# prescaled_trigger.net
KiCad netlist of a schematic drawn in EAGLE
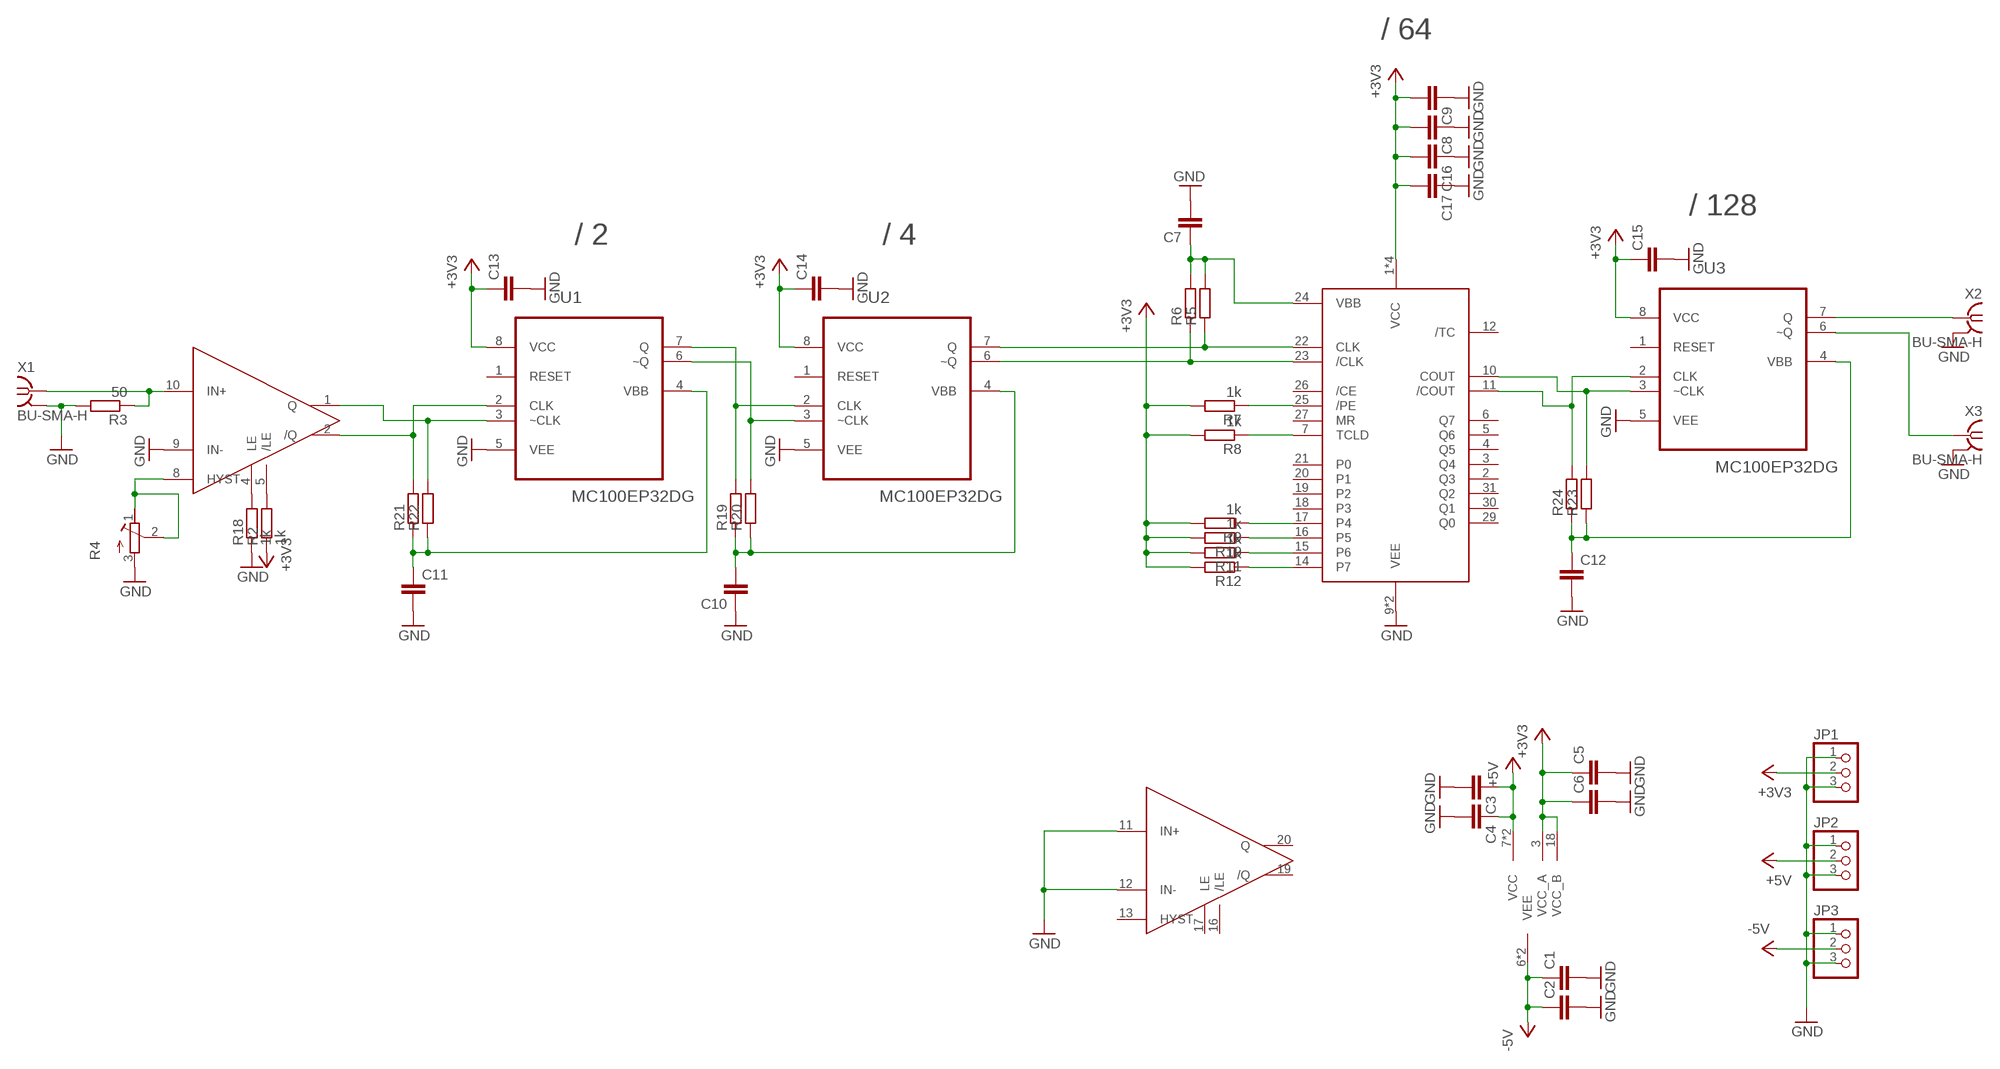
[diagram p0: schematic, sheet 1]

(export (version "E")
  (design (tool "Eeschema 10.0.6"))
  (components
    (comp (ref "C1")
      (value "C-EUC0805")
      (footprint "eagle-import:C0805")
      (libsource (lib "eagle-import") (part "C-EUC0805"))
    )
    (comp (ref "C2")
      (value "C-EUC0805")
      (footprint "eagle-import:C0805")
      (libsource (lib "eagle-import") (part "C-EUC0805"))
    )
    (comp (ref "C3")
      (value "C-EUC0805")
      (footprint "eagle-import:C0805")
      (libsource (lib "eagle-import") (part "C-EUC0805"))
    )
    (comp (ref "C4")
      (value "C-EUC0805")
      (footprint "eagle-import:C0805")
      (libsource (lib "eagle-import") (part "C-EUC0805"))
    )
    (comp (ref "C5")
      (value "C-EUC0805")
      (footprint "eagle-import:C0805")
      (libsource (lib "eagle-import") (part "C-EUC0805"))
    )
    (comp (ref "C6")
      (value "C-EUC0805")
      (footprint "eagle-import:C0805")
      (libsource (lib "eagle-import") (part "C-EUC0805"))
    )
    (comp (ref "C7")
      (value "C-EUC0805")
      (footprint "eagle-import:C0805")
      (libsource (lib "eagle-import") (part "C-EUC0805"))
    )
    (comp (ref "C8")
      (value "C-EUC0805")
      (footprint "eagle-import:C0805")
      (libsource (lib "eagle-import") (part "C-EUC0805"))
    )
    (comp (ref "C9")
      (value "C-EUC0805")
      (footprint "eagle-import:C0805")
      (libsource (lib "eagle-import") (part "C-EUC0805"))
    )
    (comp (ref "C10")
      (value "C-EUC0805")
      (footprint "eagle-import:C0805")
      (libsource (lib "eagle-import") (part "C-EUC0805"))
    )
    (comp (ref "C11")
      (value "C-EUC0805")
      (footprint "eagle-import:C0805")
      (libsource (lib "eagle-import") (part "C-EUC0805"))
    )
    (comp (ref "C12")
      (value "C-EUC0805")
      (footprint "eagle-import:C0805")
      (libsource (lib "eagle-import") (part "C-EUC0805"))
    )
    (comp (ref "C13")
      (value "C-EUC0805")
      (footprint "eagle-import:C0805")
      (libsource (lib "eagle-import") (part "C-EUC0805"))
    )
    (comp (ref "C14")
      (value "C-EUC0805")
      (footprint "eagle-import:C0805")
      (libsource (lib "eagle-import") (part "C-EUC0805"))
    )
    (comp (ref "C15")
      (value "C-EUC0805")
      (footprint "eagle-import:C0805")
      (libsource (lib "eagle-import") (part "C-EUC0805"))
    )
    (comp (ref "C16")
      (value "C-EUC0805")
      (footprint "eagle-import:C0805")
      (libsource (lib "eagle-import") (part "C-EUC0805"))
    )
    (comp (ref "C17")
      (value "C-EUC0805")
      (footprint "eagle-import:C0805")
      (libsource (lib "eagle-import") (part "C-EUC0805"))
    )
    (comp (ref "JP1")
      (value "PINHD-1X3")
      (footprint "eagle-import:1X03")
      (libsource (lib "eagle-import") (part "PINHD-1X3"))
    )
    (comp (ref "JP2")
      (value "PINHD-1X3")
      (footprint "eagle-import:1X03")
      (libsource (lib "eagle-import") (part "PINHD-1X3"))
    )
    (comp (ref "JP3")
      (value "PINHD-1X3")
      (footprint "eagle-import:1X03")
      (libsource (lib "eagle-import") (part "PINHD-1X3"))
    )
    (comp (ref "R2")
      (value "1k")
      (footprint "eagle-import:M0805")
      (libsource (lib "eagle-import") (part "R-EU_M0805"))
    )
    (comp (ref "R3")
      (value "50")
      (footprint "eagle-import:M0805")
      (libsource (lib "eagle-import") (part "R-EU_M0805"))
    )
    (comp (ref "R4")
      (value "R-TRIMMT18")
      (footprint "eagle-import:RTRIMT18")
      (libsource (lib "eagle-import") (part "R-TRIMMT18"))
    )
    (comp (ref "R5")
      (value "R-EU_M1206")
      (footprint "eagle-import:M1206")
      (libsource (lib "eagle-import") (part "R-EU_M1206"))
    )
    (comp (ref "R6")
      (value "R-EU_M1206")
      (footprint "eagle-import:M1206")
      (libsource (lib "eagle-import") (part "R-EU_M1206"))
    )
    (comp (ref "R7")
      (value "1k")
      (footprint "eagle-import:M0805")
      (libsource (lib "eagle-import") (part "R-EU_M0805"))
    )
    (comp (ref "R8")
      (value "1k")
      (footprint "eagle-import:M0805")
      (libsource (lib "eagle-import") (part "R-EU_M0805"))
    )
    (comp (ref "R9")
      (value "1k")
      (footprint "eagle-import:M0805")
      (libsource (lib "eagle-import") (part "R-EU_M0805"))
    )
    (comp (ref "R10")
      (value "1k")
      (footprint "eagle-import:M0805")
      (libsource (lib "eagle-import") (part "R-EU_M0805"))
    )
    (comp (ref "R11")
      (value "1k")
      (footprint "eagle-import:M0805")
      (libsource (lib "eagle-import") (part "R-EU_M0805"))
    )
    (comp (ref "R12")
      (value "1k")
      (footprint "eagle-import:M0805")
      (libsource (lib "eagle-import") (part "R-EU_M0805"))
    )
    (comp (ref "R18")
      (value "1k")
      (footprint "eagle-import:M0805")
      (libsource (lib "eagle-import") (part "R-EU_M0805"))
    )
    (comp (ref "R19")
      (value "R-EU_M1206")
      (footprint "eagle-import:M1206")
      (libsource (lib "eagle-import") (part "R-EU_M1206"))
    )
    (comp (ref "R20")
      (value "R-EU_M1206")
      (footprint "eagle-import:M1206")
      (libsource (lib "eagle-import") (part "R-EU_M1206"))
    )
    (comp (ref "R21")
      (value "R-EU_M1206")
      (footprint "eagle-import:M1206")
      (libsource (lib "eagle-import") (part "R-EU_M1206"))
    )
    (comp (ref "R22")
      (value "R-EU_M1206")
      (footprint "eagle-import:M1206")
      (libsource (lib "eagle-import") (part "R-EU_M1206"))
    )
    (comp (ref "R23")
      (value "R-EU_M1206")
      (footprint "eagle-import:M1206")
      (libsource (lib "eagle-import") (part "R-EU_M1206"))
    )
    (comp (ref "R24")
      (value "R-EU_M1206")
      (footprint "eagle-import:M1206")
      (libsource (lib "eagle-import") (part "R-EU_M1206"))
    )
    (comp (ref "U$1")
      (value "MAX9601")
      (footprint "eagle-import:SSOP20DB")
      (libsource (lib "eagle-import") (part "MAX9601"))
    )
    (comp (ref "U$2")
      (value "MC100EP016")
      (footprint "eagle-import:QFP80P900X900X160-32N")
      (libsource (lib "eagle-import") (part "MC100EP016"))
    )
    (comp (ref "U1")
      (value "MC100EP32DG")
      (footprint "eagle-import:SOIC127P600X175-8N")
      (libsource (lib "eagle-import") (part "MC100EP32DG"))
    )
    (comp (ref "U2")
      (value "MC100EP32DG")
      (footprint "eagle-import:SOIC127P600X175-8N")
      (libsource (lib "eagle-import") (part "MC100EP32DG"))
    )
    (comp (ref "U3")
      (value "MC100EP32DG")
      (footprint "eagle-import:SOIC127P600X175-8N")
      (libsource (lib "eagle-import") (part "MC100EP32DG"))
    )
    (comp (ref "X1")
      (value "BU-SMA-H")
      (footprint "eagle-import:BU-SMA-H")
      (libsource (lib "eagle-import") (part "BU-SMA-H"))
    )
    (comp (ref "X2")
      (value "BU-SMA-H")
      (footprint "eagle-import:BU-SMA-H")
      (libsource (lib "eagle-import") (part "BU-SMA-H"))
    )
    (comp (ref "X3")
      (value "BU-SMA-H")
      (footprint "eagle-import:BU-SMA-H")
      (libsource (lib "eagle-import") (part "BU-SMA-H"))
    )
  )
  (nets
    (net (code "1") (name "+3V3") (class "Default")
      (node (ref "C13") (pin "1") (pinfunction "1_1") (pintype "passive"))
      (node (ref "C14") (pin "1") (pinfunction "1_1") (pintype "passive"))
      (node (ref "C15") (pin "1") (pinfunction "1_1") (pintype "passive"))
      (node (ref "C16") (pin "2") (pinfunction "2_2") (pintype "passive"))
      (node (ref "C17") (pin "2") (pinfunction "2_2") (pintype "passive"))
      (node (ref "C5") (pin "1") (pinfunction "1_1") (pintype "passive"))
      (node (ref "C6") (pin "1") (pinfunction "1_1") (pintype "passive"))
      (node (ref "C8") (pin "2") (pinfunction "2_2") (pintype "passive"))
      (node (ref "C9") (pin "2") (pinfunction "2_2") (pintype "passive"))
      (node (ref "JP1") (pin "2") (pinfunction "2_2") (pintype "passive"))
      (node (ref "R10") (pin "2") (pinfunction "2_2") (pintype "passive"))
      (node (ref "R11") (pin "2") (pinfunction "2_2") (pintype "passive"))
      (node (ref "R12") (pin "2") (pinfunction "2_2") (pintype "passive"))
      (node (ref "R2") (pin "1") (pinfunction "1_1") (pintype "passive"))
      (node (ref "R7") (pin "2") (pinfunction "2_2") (pintype "passive"))
      (node (ref "R8") (pin "2") (pinfunction "2_2") (pintype "passive"))
      (node (ref "R9") (pin "2") (pinfunction "2_2") (pintype "passive"))
      (node (ref "U$1") (pin "18") (pinfunction "VCC_B_18") (pintype "bidirectional"))
      (node (ref "U$1") (pin "3") (pinfunction "VCC_A_3") (pintype "bidirectional"))
      (node (ref "U$2") (pin "1") (pinfunction "VCC_1") (pintype "bidirectional"))
      (node (ref "U$2") (pin "13") (pinfunction "VCC_13") (pintype "bidirectional"))
      (node (ref "U$2") (pin "32") (pinfunction "VCC_32") (pintype "bidirectional"))
      (node (ref "U$2") (pin "8") (pinfunction "VCC_8") (pintype "bidirectional"))
      (node (ref "U1") (pin "8") (pinfunction "VCC_8") (pintype "power_in"))
      (node (ref "U2") (pin "8") (pinfunction "VCC_8") (pintype "power_in"))
      (node (ref "U3") (pin "8") (pinfunction "VCC_8") (pintype "power_in"))
    )
    (net (code "2") (name "+5V") (class "Default")
      (node (ref "C3") (pin "1") (pinfunction "1_1") (pintype "passive"))
      (node (ref "C4") (pin "1") (pinfunction "1_1") (pintype "passive"))
      (node (ref "JP2") (pin "2") (pinfunction "2_2") (pintype "passive"))
      (node (ref "U$1") (pin "14") (pinfunction "VCC_14") (pintype "bidirectional"))
      (node (ref "U$1") (pin "7") (pinfunction "VCC_7") (pintype "bidirectional"))
    )
    (net (code "3") (name "-5V") (class "Default")
      (node (ref "C1") (pin "1") (pinfunction "1_1") (pintype "passive"))
      (node (ref "C2") (pin "1") (pinfunction "1_1") (pintype "passive"))
      (node (ref "JP3") (pin "2") (pinfunction "2_2") (pintype "passive"))
      (node (ref "U$1") (pin "15") (pinfunction "VEE_15") (pintype "bidirectional"))
      (node (ref "U$1") (pin "6") (pinfunction "VEE_6") (pintype "bidirectional"))
    )
    (net (code "4") (name "GND") (class "Default")
      (node (ref "C1") (pin "2") (pinfunction "2_2") (pintype "passive"))
      (node (ref "C10") (pin "1") (pinfunction "1_1") (pintype "passive"))
      (node (ref "C11") (pin "2") (pinfunction "2_2") (pintype "passive"))
      (node (ref "C12") (pin "2") (pinfunction "2_2") (pintype "passive"))
      (node (ref "C13") (pin "2") (pinfunction "2_2") (pintype "passive"))
      (node (ref "C14") (pin "2") (pinfunction "2_2") (pintype "passive"))
      (node (ref "C15") (pin "2") (pinfunction "2_2") (pintype "passive"))
      (node (ref "C16") (pin "1") (pinfunction "1_1") (pintype "passive"))
      (node (ref "C17") (pin "1") (pinfunction "1_1") (pintype "passive"))
      (node (ref "C2") (pin "2") (pinfunction "2_2") (pintype "passive"))
      (node (ref "C3") (pin "2") (pinfunction "2_2") (pintype "passive"))
      (node (ref "C4") (pin "2") (pinfunction "2_2") (pintype "passive"))
      (node (ref "C5") (pin "2") (pinfunction "2_2") (pintype "passive"))
      (node (ref "C6") (pin "2") (pinfunction "2_2") (pintype "passive"))
      (node (ref "C7") (pin "2") (pinfunction "2_2") (pintype "passive"))
      (node (ref "C8") (pin "1") (pinfunction "1_1") (pintype "passive"))
      (node (ref "C9") (pin "1") (pinfunction "1_1") (pintype "passive"))
      (node (ref "JP1") (pin "1") (pinfunction "1_1") (pintype "passive"))
      (node (ref "JP1") (pin "3") (pinfunction "3_3") (pintype "passive"))
      (node (ref "JP2") (pin "1") (pinfunction "1_1") (pintype "passive"))
      (node (ref "JP2") (pin "3") (pinfunction "3_3") (pintype "passive"))
      (node (ref "JP3") (pin "1") (pinfunction "1_1") (pintype "passive"))
      (node (ref "JP3") (pin "3") (pinfunction "3_3") (pintype "passive"))
      (node (ref "R18") (pin "1") (pinfunction "1_1") (pintype "passive"))
      (node (ref "R3") (pin "2") (pinfunction "2_2") (pintype "passive"))
      (node (ref "R4") (pin "3") (pinfunction "E_3") (pintype "passive"))
      (node (ref "U$1") (pin "11") (pinfunction "IN+_11") (pintype "bidirectional"))
      (node (ref "U$1") (pin "12") (pinfunction "IN-_12") (pintype "bidirectional"))
      (node (ref "U$1") (pin "9") (pinfunction "IN-_9") (pintype "bidirectional"))
      (node (ref "U$2") (pin "28") (pinfunction "VEE_28") (pintype "bidirectional"))
      (node (ref "U$2") (pin "9") (pinfunction "VEE_9") (pintype "bidirectional"))
      (node (ref "U1") (pin "5") (pinfunction "VEE_5") (pintype "power_in"))
      (node (ref "U2") (pin "5") (pinfunction "VEE_5") (pintype "power_in"))
      (node (ref "U3") (pin "5") (pinfunction "VEE_5") (pintype "power_in"))
      (node (ref "X1") (pin "2") (pinfunction "2_2") (pintype "passive"))
      (node (ref "X1") (pin "3") (pinfunction "2_3") (pintype "passive"))
      (node (ref "X1") (pin "4") (pinfunction "2_4") (pintype "passive"))
      (node (ref "X1") (pin "5") (pinfunction "2_5") (pintype "passive"))
      (node (ref "X2") (pin "2") (pinfunction "2_2") (pintype "passive"))
      (node (ref "X2") (pin "3") (pinfunction "2_3") (pintype "passive"))
      (node (ref "X2") (pin "4") (pinfunction "2_4") (pintype "passive"))
      (node (ref "X2") (pin "5") (pinfunction "2_5") (pintype "passive"))
      (node (ref "X3") (pin "2") (pinfunction "2_2") (pintype "passive"))
      (node (ref "X3") (pin "3") (pinfunction "2_3") (pintype "passive"))
      (node (ref "X3") (pin "4") (pinfunction "2_4") (pintype "passive"))
      (node (ref "X3") (pin "5") (pinfunction "2_5") (pintype "passive"))
    )
    (net (code "5") (name "Net-(R4-A)") (class "Default")
      (node (ref "R4") (pin "1") (pinfunction "A_1") (pintype "passive"))
      (node (ref "R4") (pin "2") (pinfunction "S_2") (pintype "passive"))
      (node (ref "U$1") (pin "8") (pinfunction "HYST_8") (pintype "bidirectional"))
    )
    (net (code "6") (name "Net-(U$1A-IN+)") (class "Default")
      (node (ref "R3") (pin "1") (pinfunction "1_1") (pintype "passive"))
      (node (ref "U$1") (pin "10") (pinfunction "IN+_10") (pintype "bidirectional"))
      (node (ref "X1") (pin "1") (pinfunction "1_1") (pintype "passive"))
    )
    (net (code "7") (name "Net-(U$1A-LE)") (class "Default")
      (node (ref "R18") (pin "2") (pinfunction "2_2") (pintype "passive"))
      (node (ref "U$1") (pin "4") (pinfunction "LE_4") (pintype "bidirectional"))
    )
    (net (code "8") (name "Net-(U$1A-Q)") (class "Default")
      (node (ref "R22") (pin "2") (pinfunction "2_2") (pintype "passive"))
      (node (ref "U$1") (pin "1") (pinfunction "Q_1") (pintype "bidirectional"))
      (node (ref "U1") (pin "3") (pinfunction "~{CLK}_3") (pintype "input"))
    )
    (net (code "9") (name "Net-(U$1A-{slash}LE)") (class "Default")
      (node (ref "R2") (pin "2") (pinfunction "2_2") (pintype "passive"))
      (node (ref "U$1") (pin "5") (pinfunction "/LE_5") (pintype "bidirectional"))
    )
    (net (code "10") (name "Net-(U$1A-{slash}Q)") (class "Default")
      (node (ref "R21") (pin "2") (pinfunction "2_2") (pintype "passive"))
      (node (ref "U$1") (pin "2") (pinfunction "/Q_2") (pintype "bidirectional"))
      (node (ref "U1") (pin "2") (pinfunction "CLK_2") (pintype "input"))
    )
    (net (code "11") (name "Net-(U$2-CLK)") (class "Default")
      (node (ref "R5") (pin "1") (pinfunction "1_1") (pintype "passive"))
      (node (ref "U$2") (pin "22") (pinfunction "CLK_22") (pintype "bidirectional"))
      (node (ref "U2") (pin "7") (pinfunction "Q_7") (pintype "output"))
    )
    (net (code "12") (name "Net-(U$2-COUT)") (class "Default")
      (node (ref "R23") (pin "2") (pinfunction "2_2") (pintype "passive"))
      (node (ref "U$2") (pin "10") (pinfunction "COUT_10") (pintype "bidirectional"))
      (node (ref "U3") (pin "3") (pinfunction "~{CLK}_3") (pintype "input"))
    )
    (net (code "13") (name "Net-(U$2-P4)") (class "Default")
      (node (ref "R9") (pin "1") (pinfunction "1_1") (pintype "passive"))
      (node (ref "U$2") (pin "17") (pinfunction "P4_17") (pintype "bidirectional"))
    )
    (net (code "14") (name "Net-(U$2-P5)") (class "Default")
      (node (ref "R10") (pin "1") (pinfunction "1_1") (pintype "passive"))
      (node (ref "U$2") (pin "16") (pinfunction "P5_16") (pintype "bidirectional"))
    )
    (net (code "15") (name "Net-(U$2-P6)") (class "Default")
      (node (ref "R11") (pin "1") (pinfunction "1_1") (pintype "passive"))
      (node (ref "U$2") (pin "15") (pinfunction "P6_15") (pintype "bidirectional"))
    )
    (net (code "16") (name "Net-(U$2-P7)") (class "Default")
      (node (ref "R12") (pin "1") (pinfunction "1_1") (pintype "passive"))
      (node (ref "U$2") (pin "14") (pinfunction "P7_14") (pintype "bidirectional"))
    )
    (net (code "17") (name "Net-(U$2-TCLD)") (class "Default")
      (node (ref "R8") (pin "1") (pinfunction "1_1") (pintype "passive"))
      (node (ref "U$2") (pin "7") (pinfunction "TCLD_7") (pintype "bidirectional"))
    )
    (net (code "18") (name "Net-(U$2-VBB)") (class "Default")
      (node (ref "C7") (pin "1") (pinfunction "1_1") (pintype "passive"))
      (node (ref "R5") (pin "2") (pinfunction "2_2") (pintype "passive"))
      (node (ref "R6") (pin "2") (pinfunction "2_2") (pintype "passive"))
      (node (ref "U$2") (pin "24") (pinfunction "VBB_24") (pintype "bidirectional"))
    )
    (net (code "19") (name "Net-(U$2-{slash}CLK)") (class "Default")
      (node (ref "R6") (pin "1") (pinfunction "1_1") (pintype "passive"))
      (node (ref "U$2") (pin "23") (pinfunction "/CLK_23") (pintype "bidirectional"))
      (node (ref "U2") (pin "6") (pinfunction "~{Q}_6") (pintype "output"))
    )
    (net (code "20") (name "Net-(U$2-{slash}COUT)") (class "Default")
      (node (ref "R24") (pin "2") (pinfunction "2_2") (pintype "passive"))
      (node (ref "U$2") (pin "11") (pinfunction "/COUT_11") (pintype "bidirectional"))
      (node (ref "U3") (pin "2") (pinfunction "CLK_2") (pintype "input"))
    )
    (net (code "21") (name "Net-(U$2-{slash}PE)") (class "Default")
      (node (ref "R7") (pin "1") (pinfunction "1_1") (pintype "passive"))
      (node (ref "U$2") (pin "25") (pinfunction "/PE_25") (pintype "bidirectional"))
    )
    (net (code "22") (name "Net-(U1-Q)") (class "Default")
      (node (ref "R19") (pin "2") (pinfunction "2_2") (pintype "passive"))
      (node (ref "U1") (pin "7") (pinfunction "Q_7") (pintype "output"))
      (node (ref "U2") (pin "2") (pinfunction "CLK_2") (pintype "input"))
    )
    (net (code "23") (name "Net-(U1-VBB)") (class "Default")
      (node (ref "C11") (pin "1") (pinfunction "1_1") (pintype "passive"))
      (node (ref "R21") (pin "1") (pinfunction "1_1") (pintype "passive"))
      (node (ref "R22") (pin "1") (pinfunction "1_1") (pintype "passive"))
      (node (ref "U1") (pin "4") (pinfunction "VBB_4") (pintype "output"))
    )
    (net (code "24") (name "Net-(U1-~{Q})") (class "Default")
      (node (ref "R20") (pin "2") (pinfunction "2_2") (pintype "passive"))
      (node (ref "U1") (pin "6") (pinfunction "~{Q}_6") (pintype "output"))
      (node (ref "U2") (pin "3") (pinfunction "~{CLK}_3") (pintype "input"))
    )
    (net (code "25") (name "Net-(U2-VBB)") (class "Default")
      (node (ref "C10") (pin "2") (pinfunction "2_2") (pintype "passive"))
      (node (ref "R19") (pin "1") (pinfunction "1_1") (pintype "passive"))
      (node (ref "R20") (pin "1") (pinfunction "1_1") (pintype "passive"))
      (node (ref "U2") (pin "4") (pinfunction "VBB_4") (pintype "output"))
    )
    (net (code "26") (name "Net-(U3-Q)") (class "Default")
      (node (ref "U3") (pin "7") (pinfunction "Q_7") (pintype "output"))
      (node (ref "X2") (pin "1") (pinfunction "1_1") (pintype "passive"))
    )
    (net (code "27") (name "Net-(U3-VBB)") (class "Default")
      (node (ref "C12") (pin "1") (pinfunction "1_1") (pintype "passive"))
      (node (ref "R23") (pin "1") (pinfunction "1_1") (pintype "passive"))
      (node (ref "R24") (pin "1") (pinfunction "1_1") (pintype "passive"))
      (node (ref "U3") (pin "4") (pinfunction "VBB_4") (pintype "output"))
    )
    (net (code "28") (name "Net-(U3-~{Q})") (class "Default")
      (node (ref "U3") (pin "6") (pinfunction "~{Q}_6") (pintype "output"))
      (node (ref "X3") (pin "1") (pinfunction "1_1") (pintype "passive"))
    )
    (net (code "29") (name "unconnected-(U$1B-HYST-Pad13)") (class "Default")
      (node (ref "U$1") (pin "13") (pinfunction "HYST_13") (pintype "bidirectional"))
    )
    (net (code "30") (name "unconnected-(U$1B-LE-Pad17)") (class "Default")
      (node (ref "U$1") (pin "17") (pinfunction "LE_17") (pintype "bidirectional"))
    )
    (net (code "31") (name "unconnected-(U$1B-Q-Pad20)") (class "Default")
      (node (ref "U$1") (pin "20") (pinfunction "Q_20") (pintype "bidirectional"))
    )
    (net (code "32") (name "unconnected-(U$1B-{slash}LE-Pad16)") (class "Default")
      (node (ref "U$1") (pin "16") (pinfunction "/LE_16") (pintype "bidirectional"))
    )
    (net (code "33") (name "unconnected-(U$1B-{slash}Q-Pad19)") (class "Default")
      (node (ref "U$1") (pin "19") (pinfunction "/Q_19") (pintype "bidirectional"))
    )
    (net (code "34") (name "unconnected-(U$2-MR-Pad27)") (class "Default")
      (node (ref "U$2") (pin "27") (pinfunction "MR_27") (pintype "bidirectional"))
    )
    (net (code "35") (name "unconnected-(U$2-P0-Pad21)") (class "Default")
      (node (ref "U$2") (pin "21") (pinfunction "P0_21") (pintype "bidirectional"))
    )
    (net (code "36") (name "unconnected-(U$2-P1-Pad20)") (class "Default")
      (node (ref "U$2") (pin "20") (pinfunction "P1_20") (pintype "bidirectional"))
    )
    (net (code "37") (name "unconnected-(U$2-P2-Pad19)") (class "Default")
      (node (ref "U$2") (pin "19") (pinfunction "P2_19") (pintype "bidirectional"))
    )
    (net (code "38") (name "unconnected-(U$2-P3-Pad18)") (class "Default")
      (node (ref "U$2") (pin "18") (pinfunction "P3_18") (pintype "bidirectional"))
    )
    (net (code "39") (name "unconnected-(U$2-Q0-Pad29)") (class "Default")
      (node (ref "U$2") (pin "29") (pinfunction "Q0_29") (pintype "bidirectional"))
    )
    (net (code "40") (name "unconnected-(U$2-Q1-Pad30)") (class "Default")
      (node (ref "U$2") (pin "30") (pinfunction "Q1_30") (pintype "bidirectional"))
    )
    (net (code "41") (name "unconnected-(U$2-Q2-Pad31)") (class "Default")
      (node (ref "U$2") (pin "31") (pinfunction "Q2_31") (pintype "bidirectional"))
    )
    (net (code "42") (name "unconnected-(U$2-Q3-Pad2)") (class "Default")
      (node (ref "U$2") (pin "2") (pinfunction "Q3_2") (pintype "bidirectional"))
    )
    (net (code "43") (name "unconnected-(U$2-Q4-Pad3)") (class "Default")
      (node (ref "U$2") (pin "3") (pinfunction "Q4_3") (pintype "bidirectional"))
    )
    (net (code "44") (name "unconnected-(U$2-Q5-Pad4)") (class "Default")
      (node (ref "U$2") (pin "4") (pinfunction "Q5_4") (pintype "bidirectional"))
    )
    (net (code "45") (name "unconnected-(U$2-Q6-Pad5)") (class "Default")
      (node (ref "U$2") (pin "5") (pinfunction "Q6_5") (pintype "bidirectional"))
    )
    (net (code "46") (name "unconnected-(U$2-Q7-Pad6)") (class "Default")
      (node (ref "U$2") (pin "6") (pinfunction "Q7_6") (pintype "bidirectional"))
    )
    (net (code "47") (name "unconnected-(U$2-{slash}CE-Pad26)") (class "Default")
      (node (ref "U$2") (pin "26") (pinfunction "/CE_26") (pintype "bidirectional"))
    )
    (net (code "48") (name "unconnected-(U$2-{slash}TC-Pad12)") (class "Default")
      (node (ref "U$2") (pin "12") (pinfunction "/TC_12") (pintype "bidirectional"))
    )
    (net (code "49") (name "unconnected-(U1-RESET-Pad1)") (class "Default")
      (node (ref "U1") (pin "1") (pinfunction "RESET_1") (pintype "input"))
    )
    (net (code "50") (name "unconnected-(U2-RESET-Pad1)") (class "Default")
      (node (ref "U2") (pin "1") (pinfunction "RESET_1") (pintype "input"))
    )
    (net (code "51") (name "unconnected-(U3-RESET-Pad1)") (class "Default")
      (node (ref "U3") (pin "1") (pinfunction "RESET_1") (pintype "input"))
    )
  )
)
